# schematv2.net
KiCad netlist of a schematic drawn in EAGLE
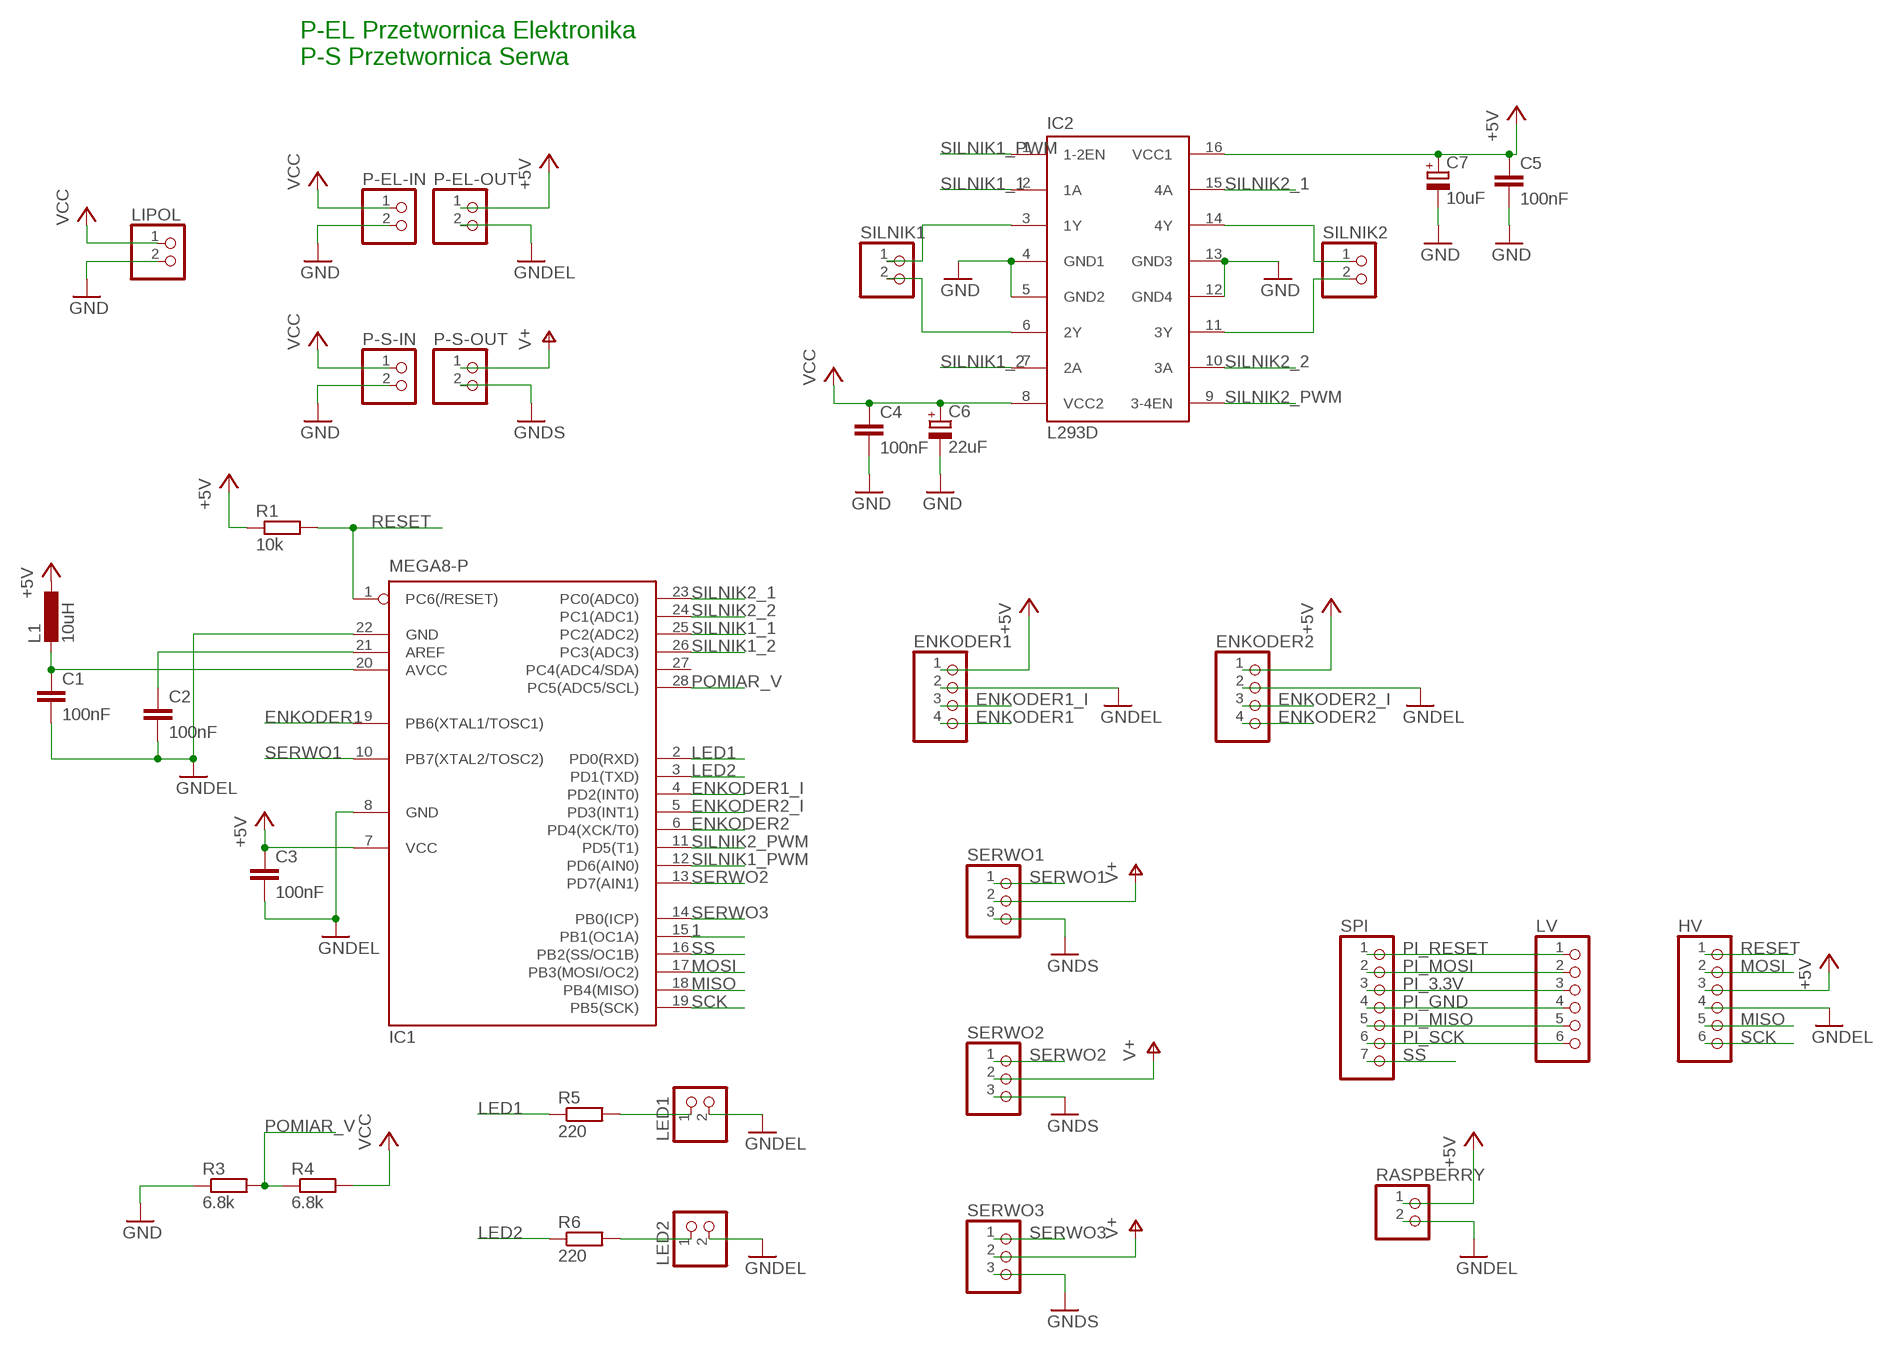
[diagram p0: schematic, sheet 1]

(export (version "E")
  (design (tool "Eeschema 10.0.6"))
  (components
    (comp (ref "C1")
      (value "100nF")
      (footprint "eagle-import:C050-030X075")
      (libsource (lib "eagle-import") (part "C-EU050-030X075"))
    )
    (comp (ref "C2")
      (value "100nF")
      (footprint "eagle-import:C025-030X050")
      (libsource (lib "eagle-import") (part "C-EU025-030X050"))
    )
    (comp (ref "C3")
      (value "100nF")
      (footprint "eagle-import:C025-030X050")
      (libsource (lib "eagle-import") (part "C-EU025-030X050"))
    )
    (comp (ref "C4")
      (value "100nF")
      (footprint "eagle-import:C025-030X050")
      (libsource (lib "eagle-import") (part "C-EU025-030X050"))
    )
    (comp (ref "C5")
      (value "100nF")
      (footprint "eagle-import:C025-030X050")
      (libsource (lib "eagle-import") (part "C-EU025-030X050"))
    )
    (comp (ref "C6")
      (value "22uF")
      (footprint "eagle-import:E2,5-5")
      (libsource (lib "eagle-import") (part "CPOL-EUE2.5-5"))
    )
    (comp (ref "C7")
      (value "10uF")
      (footprint "eagle-import:E2,5-5")
      (libsource (lib "eagle-import") (part "CPOL-EUE2.5-5"))
    )
    (comp (ref "ENKODER1")
      (value "PINHD-1X4")
      (footprint "eagle-import:1X04")
      (libsource (lib "eagle-import") (part "PINHD-1X4"))
    )
    (comp (ref "ENKODER2")
      (value "PINHD-1X4")
      (footprint "eagle-import:1X04")
      (libsource (lib "eagle-import") (part "PINHD-1X4"))
    )
    (comp (ref "HV")
      (value "PINHD-1X6")
      (footprint "eagle-import:1X06")
      (libsource (lib "eagle-import") (part "PINHD-1X6"))
    )
    (comp (ref "IC1")
      (value "MEGA8-P")
      (footprint "eagle-import:DIL28-3")
      (libsource (lib "eagle-import") (part "MEGA8-P"))
    )
    (comp (ref "IC2")
      (value "L293D")
      (footprint "eagle-import:DIL16")
      (libsource (lib "eagle-import") (part "L293D"))
    )
    (comp (ref "L1")
      (value "10uH")
      (footprint "eagle-import:0204_7")
      (libsource (lib "eagle-import") (part "L-EU0204/7"))
    )
    (comp (ref "LED1")
      (value "PINHD-1X2")
      (footprint "eagle-import:1X02")
      (libsource (lib "eagle-import") (part "PINHD-1X2"))
    )
    (comp (ref "LED2")
      (value "PINHD-1X2")
      (footprint "eagle-import:1X02")
      (libsource (lib "eagle-import") (part "PINHD-1X2"))
    )
    (comp (ref "LIPOL")
      (value "PINHD-1X2")
      (footprint "eagle-import:1X02")
      (libsource (lib "eagle-import") (part "PINHD-1X2"))
    )
    (comp (ref "LV")
      (value "PINHD-1X6")
      (footprint "eagle-import:1X06")
      (libsource (lib "eagle-import") (part "PINHD-1X6"))
    )
    (comp (ref "P-EL-IN")
      (value "PINHD-1X2")
      (footprint "eagle-import:1X02")
      (libsource (lib "eagle-import") (part "PINHD-1X2"))
    )
    (comp (ref "P-EL-OUT")
      (value "PINHD-1X2")
      (footprint "eagle-import:1X02")
      (libsource (lib "eagle-import") (part "PINHD-1X2"))
    )
    (comp (ref "P-S-IN")
      (value "PINHD-1X2")
      (footprint "eagle-import:1X02")
      (libsource (lib "eagle-import") (part "PINHD-1X2"))
    )
    (comp (ref "P-S-OUT")
      (value "PINHD-1X2")
      (footprint "eagle-import:1X02")
      (libsource (lib "eagle-import") (part "PINHD-1X2"))
    )
    (comp (ref "R1")
      (value "10k")
      (footprint "eagle-import:0204_7")
      (libsource (lib "eagle-import") (part "R-EU_0204/7"))
    )
    (comp (ref "R3")
      (value "6.8k")
      (footprint "eagle-import:0204_7")
      (libsource (lib "eagle-import") (part "R-EU_0204/7"))
    )
    (comp (ref "R4")
      (value "6.8k")
      (footprint "eagle-import:0204_7")
      (libsource (lib "eagle-import") (part "R-EU_0204/7"))
    )
    (comp (ref "R5")
      (value "220")
      (footprint "eagle-import:0204_7")
      (libsource (lib "eagle-import") (part "R-EU_0204/7"))
    )
    (comp (ref "R6")
      (value "220")
      (footprint "eagle-import:0204_7")
      (libsource (lib "eagle-import") (part "R-EU_0204/7"))
    )
    (comp (ref "RASPBERRY")
      (value "PINHD-1X2")
      (footprint "eagle-import:1X02")
      (libsource (lib "eagle-import") (part "PINHD-1X2"))
    )
    (comp (ref "SERWO1")
      (value "PINHD-1X3")
      (footprint "eagle-import:1X03")
      (libsource (lib "eagle-import") (part "PINHD-1X3"))
    )
    (comp (ref "SERWO2")
      (value "PINHD-1X3")
      (footprint "eagle-import:1X03")
      (libsource (lib "eagle-import") (part "PINHD-1X3"))
    )
    (comp (ref "SERWO3")
      (value "PINHD-1X3")
      (footprint "eagle-import:1X03")
      (libsource (lib "eagle-import") (part "PINHD-1X3"))
    )
    (comp (ref "SILNIK1")
      (value "PINHD-1X2")
      (footprint "eagle-import:1X02")
      (libsource (lib "eagle-import") (part "PINHD-1X2"))
    )
    (comp (ref "SILNIK2")
      (value "PINHD-1X2")
      (footprint "eagle-import:1X02")
      (libsource (lib "eagle-import") (part "PINHD-1X2"))
    )
    (comp (ref "SPI")
      (value "PINHD-1X7")
      (footprint "eagle-import:1X07")
      (libsource (lib "eagle-import") (part "PINHD-1X7"))
    )
  )
  (nets
    (net (code "1") (name "+5V") (class "Default")
      (node (ref "C3") (pin "1") (pinfunction "1_1") (pintype "passive"))
      (node (ref "C5") (pin "1") (pinfunction "1_1") (pintype "passive"))
      (node (ref "C7") (pin "+") (pinfunction "+_+") (pintype "passive"))
      (node (ref "ENKODER1") (pin "1") (pinfunction "1_1") (pintype "passive"))
      (node (ref "ENKODER2") (pin "1") (pinfunction "1_1") (pintype "passive"))
      (node (ref "HV") (pin "3") (pinfunction "3_3") (pintype "passive"))
      (node (ref "IC1") (pin "7") (pinfunction "VCC_7") (pintype "power_in"))
      (node (ref "IC2") (pin "16") (pinfunction "VCC1_16") (pintype "power_in"))
      (node (ref "L1") (pin "1") (pinfunction "1_1") (pintype "passive"))
      (node (ref "P-EL-OUT") (pin "1") (pinfunction "1_1") (pintype "passive"))
      (node (ref "R1") (pin "1") (pinfunction "1_1") (pintype "passive"))
      (node (ref "RASPBERRY") (pin "1") (pinfunction "1_1") (pintype "passive"))
    )
    (net (code "2") (name "/1") (class "Default")
      (node (ref "IC1") (pin "15") (pinfunction "PB1(OC1A)_15") (pintype "bidirectional"))
    )
    (net (code "3") (name "/ENKODER1") (class "Default")
      (node (ref "ENKODER1") (pin "4") (pinfunction "4_4") (pintype "passive"))
      (node (ref "IC1") (pin "9") (pinfunction "PB6(XTAL1/TOSC1)_9") (pintype "bidirectional"))
    )
    (net (code "4") (name "/ENKODER1_I") (class "Default")
      (node (ref "ENKODER1") (pin "3") (pinfunction "3_3") (pintype "passive"))
      (node (ref "IC1") (pin "4") (pinfunction "PD2(INT0)_4") (pintype "bidirectional"))
    )
    (net (code "5") (name "/ENKODER2") (class "Default")
      (node (ref "ENKODER2") (pin "4") (pinfunction "4_4") (pintype "passive"))
      (node (ref "IC1") (pin "6") (pinfunction "PD4(XCK/T0)_6") (pintype "bidirectional"))
    )
    (net (code "6") (name "/ENKODER2_I") (class "Default")
      (node (ref "ENKODER2") (pin "3") (pinfunction "3_3") (pintype "passive"))
      (node (ref "IC1") (pin "5") (pinfunction "PD3(INT1)_5") (pintype "bidirectional"))
    )
    (net (code "7") (name "/LED1") (class "Default")
      (node (ref "IC1") (pin "2") (pinfunction "PD0(RXD)_2") (pintype "bidirectional"))
      (node (ref "R5") (pin "1") (pinfunction "1_1") (pintype "passive"))
    )
    (net (code "8") (name "/LED2") (class "Default")
      (node (ref "IC1") (pin "3") (pinfunction "PD1(TXD)_3") (pintype "bidirectional"))
      (node (ref "R6") (pin "1") (pinfunction "1_1") (pintype "passive"))
    )
    (net (code "9") (name "/MISO") (class "Default")
      (node (ref "HV") (pin "5") (pinfunction "5_5") (pintype "passive"))
      (node (ref "IC1") (pin "18") (pinfunction "PB4(MISO)_18") (pintype "bidirectional"))
    )
    (net (code "10") (name "/MOSI") (class "Default")
      (node (ref "HV") (pin "2") (pinfunction "2_2") (pintype "passive"))
      (node (ref "IC1") (pin "17") (pinfunction "PB3(MOSI/OC2)_17") (pintype "bidirectional"))
    )
    (net (code "11") (name "/PI_3.3V") (class "Default")
      (node (ref "LV") (pin "3") (pinfunction "3_3") (pintype "passive"))
      (node (ref "SPI") (pin "3") (pinfunction "3_3") (pintype "passive"))
    )
    (net (code "12") (name "/PI_GND") (class "Default")
      (node (ref "LV") (pin "4") (pinfunction "4_4") (pintype "passive"))
      (node (ref "SPI") (pin "4") (pinfunction "4_4") (pintype "passive"))
    )
    (net (code "13") (name "/PI_MISO") (class "Default")
      (node (ref "LV") (pin "5") (pinfunction "5_5") (pintype "passive"))
      (node (ref "SPI") (pin "5") (pinfunction "5_5") (pintype "passive"))
    )
    (net (code "14") (name "/PI_MOSI") (class "Default")
      (node (ref "LV") (pin "2") (pinfunction "2_2") (pintype "passive"))
      (node (ref "SPI") (pin "2") (pinfunction "2_2") (pintype "passive"))
    )
    (net (code "15") (name "/PI_RESET") (class "Default")
      (node (ref "LV") (pin "1") (pinfunction "1_1") (pintype "passive"))
      (node (ref "SPI") (pin "1") (pinfunction "1_1") (pintype "passive"))
    )
    (net (code "16") (name "/PI_SCK") (class "Default")
      (node (ref "LV") (pin "6") (pinfunction "6_6") (pintype "passive"))
      (node (ref "SPI") (pin "6") (pinfunction "6_6") (pintype "passive"))
    )
    (net (code "17") (name "/POMIAR_V") (class "Default")
      (node (ref "IC1") (pin "28") (pinfunction "PC5(ADC5/SCL)_28") (pintype "bidirectional"))
      (node (ref "R3") (pin "2") (pinfunction "2_2") (pintype "passive"))
      (node (ref "R4") (pin "1") (pinfunction "1_1") (pintype "passive"))
    )
    (net (code "18") (name "/RESET") (class "Default")
      (node (ref "HV") (pin "1") (pinfunction "1_1") (pintype "passive"))
      (node (ref "IC1") (pin "1") (pinfunction "PC6(/RESET)_1") (pintype "bidirectional"))
      (node (ref "R1") (pin "2") (pinfunction "2_2") (pintype "passive"))
    )
    (net (code "19") (name "/SCK") (class "Default")
      (node (ref "HV") (pin "6") (pinfunction "6_6") (pintype "passive"))
      (node (ref "IC1") (pin "19") (pinfunction "PB5(SCK)_19") (pintype "bidirectional"))
    )
    (net (code "20") (name "/SERWO1") (class "Default")
      (node (ref "IC1") (pin "10") (pinfunction "PB7(XTAL2/TOSC2)_10") (pintype "bidirectional"))
      (node (ref "SERWO1") (pin "1") (pinfunction "1_1") (pintype "passive"))
    )
    (net (code "21") (name "/SERWO2") (class "Default")
      (node (ref "IC1") (pin "13") (pinfunction "PD7(AIN1)_13") (pintype "bidirectional"))
      (node (ref "SERWO2") (pin "1") (pinfunction "1_1") (pintype "passive"))
    )
    (net (code "22") (name "/SERWO3") (class "Default")
      (node (ref "IC1") (pin "14") (pinfunction "PB0(ICP)_14") (pintype "bidirectional"))
      (node (ref "SERWO3") (pin "1") (pinfunction "1_1") (pintype "passive"))
    )
    (net (code "23") (name "/SILNIK1_1") (class "Default")
      (node (ref "IC1") (pin "25") (pinfunction "PC2(ADC2)_25") (pintype "bidirectional"))
      (node (ref "IC2") (pin "2") (pinfunction "1A_2") (pintype "input"))
    )
    (net (code "24") (name "/SILNIK1_2") (class "Default")
      (node (ref "IC1") (pin "26") (pinfunction "PC3(ADC3)_26") (pintype "bidirectional"))
      (node (ref "IC2") (pin "7") (pinfunction "2A_7") (pintype "input"))
    )
    (net (code "25") (name "/SILNIK1_PWM") (class "Default")
      (node (ref "IC1") (pin "12") (pinfunction "PD6(AIN0)_12") (pintype "bidirectional"))
      (node (ref "IC2") (pin "1") (pinfunction "1-2EN_1") (pintype "input"))
    )
    (net (code "26") (name "/SILNIK2_1") (class "Default")
      (node (ref "IC1") (pin "23") (pinfunction "PC0(ADC0)_23") (pintype "bidirectional"))
      (node (ref "IC2") (pin "15") (pinfunction "4A_15") (pintype "input"))
    )
    (net (code "27") (name "/SILNIK2_2") (class "Default")
      (node (ref "IC1") (pin "24") (pinfunction "PC1(ADC1)_24") (pintype "bidirectional"))
      (node (ref "IC2") (pin "10") (pinfunction "3A_10") (pintype "input"))
    )
    (net (code "28") (name "/SILNIK2_PWM") (class "Default")
      (node (ref "IC1") (pin "11") (pinfunction "PD5(T1)_11") (pintype "bidirectional"))
      (node (ref "IC2") (pin "9") (pinfunction "3-4EN_9") (pintype "input"))
    )
    (net (code "29") (name "/SS") (class "Default")
      (node (ref "IC1") (pin "16") (pinfunction "PB2(SS/OC1B)_16") (pintype "bidirectional"))
      (node (ref "SPI") (pin "7") (pinfunction "7_7") (pintype "passive"))
    )
    (net (code "30") (name "GND") (class "Default")
      (node (ref "C4") (pin "2") (pinfunction "2_2") (pintype "passive"))
      (node (ref "C5") (pin "2") (pinfunction "2_2") (pintype "passive"))
      (node (ref "C6") (pin "-") (pinfunction "-_-") (pintype "passive"))
      (node (ref "C7") (pin "-") (pinfunction "-_-") (pintype "passive"))
      (node (ref "IC2") (pin "12") (pinfunction "GND4_12") (pintype "power_in"))
      (node (ref "IC2") (pin "13") (pinfunction "GND3_13") (pintype "power_in"))
      (node (ref "IC2") (pin "4") (pinfunction "GND1_4") (pintype "power_in"))
      (node (ref "IC2") (pin "5") (pinfunction "GND2_5") (pintype "power_in"))
      (node (ref "LIPOL") (pin "2") (pinfunction "2_2") (pintype "passive"))
      (node (ref "P-EL-IN") (pin "2") (pinfunction "2_2") (pintype "passive"))
      (node (ref "P-S-IN") (pin "2") (pinfunction "2_2") (pintype "passive"))
      (node (ref "R3") (pin "1") (pinfunction "1_1") (pintype "passive"))
    )
    (net (code "31") (name "GNDEL") (class "Default")
      (node (ref "C1") (pin "2") (pinfunction "2_2") (pintype "passive"))
      (node (ref "C2") (pin "2") (pinfunction "2_2") (pintype "passive"))
      (node (ref "C3") (pin "2") (pinfunction "2_2") (pintype "passive"))
      (node (ref "ENKODER1") (pin "2") (pinfunction "2_2") (pintype "passive"))
      (node (ref "ENKODER2") (pin "2") (pinfunction "2_2") (pintype "passive"))
      (node (ref "HV") (pin "4") (pinfunction "4_4") (pintype "passive"))
      (node (ref "IC1") (pin "22") (pinfunction "GND_22") (pintype "power_in"))
      (node (ref "IC1") (pin "8") (pinfunction "GND_8") (pintype "power_in"))
      (node (ref "LED1") (pin "2") (pinfunction "2_2") (pintype "passive"))
      (node (ref "LED2") (pin "2") (pinfunction "2_2") (pintype "passive"))
      (node (ref "P-EL-OUT") (pin "2") (pinfunction "2_2") (pintype "passive"))
      (node (ref "RASPBERRY") (pin "2") (pinfunction "2_2") (pintype "passive"))
    )
    (net (code "32") (name "GNDS") (class "Default")
      (node (ref "P-S-OUT") (pin "2") (pinfunction "2_2") (pintype "passive"))
      (node (ref "SERWO1") (pin "3") (pinfunction "3_3") (pintype "passive"))
      (node (ref "SERWO2") (pin "3") (pinfunction "3_3") (pintype "passive"))
      (node (ref "SERWO3") (pin "3") (pinfunction "3_3") (pintype "passive"))
    )
    (net (code "33") (name "Net-(IC1-AREF)") (class "Default")
      (node (ref "C2") (pin "1") (pinfunction "1_1") (pintype "passive"))
      (node (ref "IC1") (pin "21") (pinfunction "AREF_21") (pintype "passive"))
    )
    (net (code "34") (name "Net-(IC1-AVCC)") (class "Default")
      (node (ref "C1") (pin "1") (pinfunction "1_1") (pintype "passive"))
      (node (ref "IC1") (pin "20") (pinfunction "AVCC_20") (pintype "power_in"))
      (node (ref "L1") (pin "2") (pinfunction "2_2") (pintype "passive"))
    )
    (net (code "35") (name "Net-(IC2-1Y)") (class "Default")
      (node (ref "IC2") (pin "3") (pinfunction "1Y_3") (pintype "output"))
      (node (ref "SILNIK1") (pin "1") (pinfunction "1_1") (pintype "passive"))
    )
    (net (code "36") (name "Net-(IC2-2Y)") (class "Default")
      (node (ref "IC2") (pin "6") (pinfunction "2Y_6") (pintype "output"))
      (node (ref "SILNIK1") (pin "2") (pinfunction "2_2") (pintype "passive"))
    )
    (net (code "37") (name "Net-(IC2-3Y)") (class "Default")
      (node (ref "IC2") (pin "11") (pinfunction "3Y_11") (pintype "output"))
      (node (ref "SILNIK2") (pin "2") (pinfunction "2_2") (pintype "passive"))
    )
    (net (code "38") (name "Net-(IC2-4Y)") (class "Default")
      (node (ref "IC2") (pin "14") (pinfunction "4Y_14") (pintype "output"))
      (node (ref "SILNIK2") (pin "1") (pinfunction "1_1") (pintype "passive"))
    )
    (net (code "39") (name "Net-(LED1-Pad1)") (class "Default")
      (node (ref "LED1") (pin "1") (pinfunction "1_1") (pintype "passive"))
      (node (ref "R5") (pin "2") (pinfunction "2_2") (pintype "passive"))
    )
    (net (code "40") (name "Net-(LED2-Pad1)") (class "Default")
      (node (ref "LED2") (pin "1") (pinfunction "1_1") (pintype "passive"))
      (node (ref "R6") (pin "2") (pinfunction "2_2") (pintype "passive"))
    )
    (net (code "41") (name "V+") (class "Default")
      (node (ref "P-S-OUT") (pin "1") (pinfunction "1_1") (pintype "passive"))
      (node (ref "SERWO1") (pin "2") (pinfunction "2_2") (pintype "passive"))
      (node (ref "SERWO2") (pin "2") (pinfunction "2_2") (pintype "passive"))
      (node (ref "SERWO3") (pin "2") (pinfunction "2_2") (pintype "passive"))
    )
    (net (code "42") (name "VCC") (class "Default")
      (node (ref "C4") (pin "1") (pinfunction "1_1") (pintype "passive"))
      (node (ref "C6") (pin "+") (pinfunction "+_+") (pintype "passive"))
      (node (ref "IC2") (pin "8") (pinfunction "VCC2_8") (pintype "power_in"))
      (node (ref "LIPOL") (pin "1") (pinfunction "1_1") (pintype "passive"))
      (node (ref "P-EL-IN") (pin "1") (pinfunction "1_1") (pintype "passive"))
      (node (ref "P-S-IN") (pin "1") (pinfunction "1_1") (pintype "passive"))
      (node (ref "R4") (pin "2") (pinfunction "2_2") (pintype "passive"))
    )
    (net (code "43") (name "unconnected-(IC1-PC4(ADC4{slash}SDA)-Pad27)") (class "Default")
      (node (ref "IC1") (pin "27") (pinfunction "PC4(ADC4/SDA)_27") (pintype "bidirectional"))
    )
  )
)
